# schematic.net
KiCad netlist of a schematic drawn in EAGLE
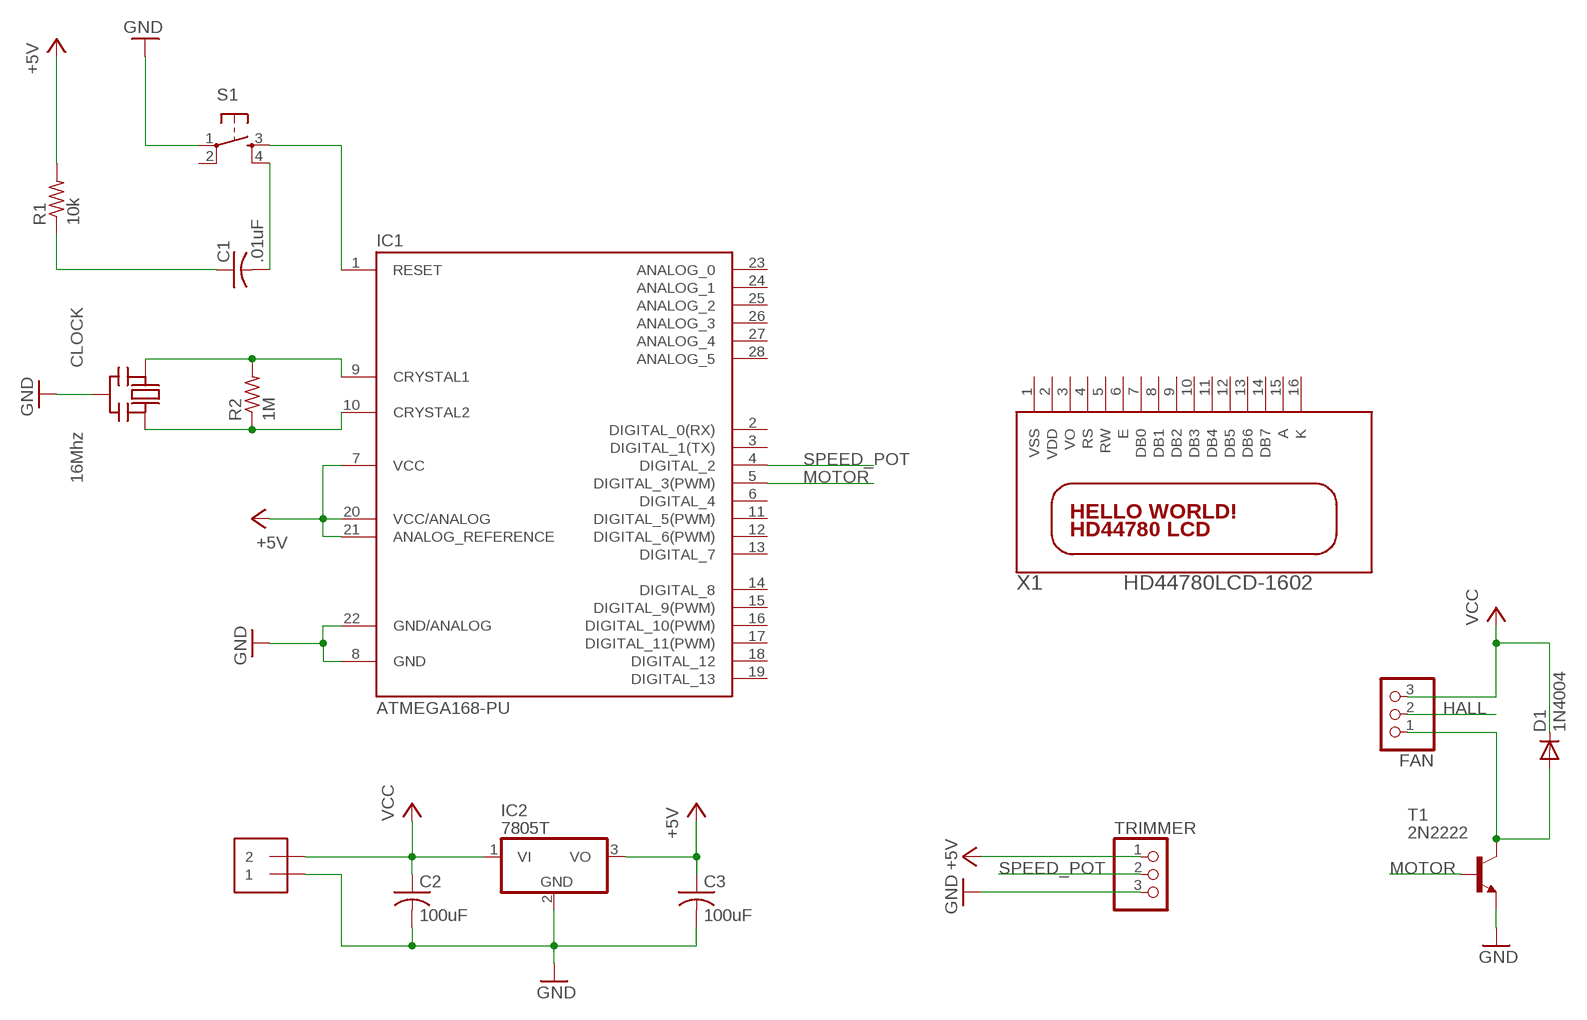
[diagram p0: schematic, sheet 1]

(export (version "E")
  (design (tool "Eeschema 10.0.6"))
  (components
    (comp (ref "C1")
      (value ".01uF")
      (footprint "eagle-import:C025-030X050")
      (libsource (lib "eagle-import") (part "C-US025-030X050"))
    )
    (comp (ref "C2")
      (value "100uF")
      (footprint "eagle-import:C025-030X050")
      (libsource (lib "eagle-import") (part "C-US025-030X050"))
    )
    (comp (ref "C3")
      (value "100uF")
      (footprint "eagle-import:C025-030X050")
      (libsource (lib "eagle-import") (part "C-US025-030X050"))
    )
    (comp (ref "CLOCK")
      (value "16Mhz")
      (footprint "eagle-import:CERM_OSC")
      (libsource (lib "eagle-import") (part "CERMOSCILL-THM"))
    )
    (comp (ref "D1")
      (value "1N4004")
      (footprint "eagle-import:DO41-10")
      (libsource (lib "eagle-import") (part "1N4004"))
    )
    (comp (ref "FAN")
      (value "PINHD-1X3CB")
      (footprint "eagle-import:1X03-CLEANBIG")
      (libsource (lib "eagle-import") (part "PINHD-1X3CB"))
    )
    (comp (ref "IC1")
      (value "ATMEGA168-PU")
      (footprint "eagle-import:DIL28-3")
      (libsource (lib "eagle-import") (part "ATMEGA168-PU"))
    )
    (comp (ref "IC2")
      (value "7805T")
      (footprint "eagle-import:TO220H")
      (libsource (lib "eagle-import") (part "78T05"))
    )
    (comp (ref "POWER")
      (value "1X2-3.5MM")
      (footprint "eagle-import:1X2-3.5MM")
      (libsource (lib "eagle-import") (part "1X2-3.5MM"))
    )
    (comp (ref "R1")
      (value "10k")
      (footprint "eagle-import:0204_7")
      (libsource (lib "eagle-import") (part "R-US_0204/7"))
    )
    (comp (ref "R2")
      (value "1M")
      (footprint "eagle-import:0204_7")
      (libsource (lib "eagle-import") (part "R-US_0204/7"))
    )
    (comp (ref "S1")
      (value "TAC_SWITCHPTH")
      (footprint "eagle-import:TACTILE-PTH")
      (libsource (lib "eagle-import") (part "TAC_SWITCHPTH"))
    )
    (comp (ref "T1")
      (value "2N2222")
      (footprint "eagle-import:TO92-EBC-OVAL")
      (libsource (lib "eagle-import") (part "2N2222"))
    )
    (comp (ref "TRIMMER")
      (value "PINHD-1X3")
      (footprint "eagle-import:1X03")
      (libsource (lib "eagle-import") (part "PINHD-1X3"))
    )
    (comp (ref "X1")
      (value "HD44780LCD-1602")
      (footprint "eagle-import:LCD1602")
      (libsource (lib "eagle-import") (part "HD44780LCD-1602"))
    )
  )
  (nets
    (net (code "1") (name "+5V") (class "Default")
      (node (ref "C3") (pin "1") (pinfunction "1_1") (pintype "passive"))
      (node (ref "IC1") (pin "20") (pinfunction "VCC/ANALOG_20") (pintype "passive"))
      (node (ref "IC1") (pin "21") (pinfunction "ANALOG_REFERENCE_21") (pintype "passive"))
      (node (ref "IC1") (pin "7") (pinfunction "VCC_7") (pintype "power_in"))
      (node (ref "IC2") (pin "3") (pinfunction "VO_3") (pintype "passive"))
      (node (ref "R1") (pin "2") (pinfunction "2_2") (pintype "passive"))
      (node (ref "TRIMMER") (pin "1") (pinfunction "1_1") (pintype "passive"))
    )
    (net (code "2") (name "/HALL") (class "Default")
      (node (ref "FAN") (pin "2") (pinfunction "2_2") (pintype "passive"))
    )
    (net (code "3") (name "/MOTOR") (class "Default")
      (node (ref "IC1") (pin "5") (pinfunction "DIGITAL_3(PWM)_5") (pintype "bidirectional"))
      (node (ref "T1") (pin "B") (pinfunction "B_B") (pintype "passive"))
    )
    (net (code "4") (name "/SPEED_POT") (class "Default")
      (node (ref "IC1") (pin "4") (pinfunction "DIGITAL_2_4") (pintype "bidirectional"))
      (node (ref "TRIMMER") (pin "2") (pinfunction "2_2") (pintype "passive"))
    )
    (net (code "5") (name "/VDD") (class "Default")
      (node (ref "X1") (pin "2") (pinfunction "VDD_2") (pintype "power_in"))
    )
    (net (code "6") (name "/VSS") (class "Default")
      (node (ref "X1") (pin "1") (pinfunction "VSS_1") (pintype "power_in"))
    )
    (net (code "7") (name "GND") (class "Default")
      (node (ref "C2") (pin "2") (pinfunction "2_2") (pintype "passive"))
      (node (ref "C3") (pin "2") (pinfunction "2_2") (pintype "passive"))
      (node (ref "CLOCK") (pin "P$2") (pinfunction "GND_P$2") (pintype "bidirectional"))
      (node (ref "IC1") (pin "22") (pinfunction "GND/ANALOG_22") (pintype "power_in"))
      (node (ref "IC1") (pin "8") (pinfunction "GND_8") (pintype "power_in"))
      (node (ref "IC2") (pin "2") (pinfunction "GND_2") (pintype "passive"))
      (node (ref "POWER") (pin "1") (pinfunction "1_1") (pintype "passive"))
      (node (ref "S1") (pin "1") (pinfunction "1_1") (pintype "passive"))
      (node (ref "T1") (pin "E") (pinfunction "E_E") (pintype "passive"))
      (node (ref "TRIMMER") (pin "3") (pinfunction "3_3") (pintype "passive"))
    )
    (net (code "8") (name "Net-(C1-Pad1)") (class "Default")
      (node (ref "C1") (pin "1") (pinfunction "1_1") (pintype "passive"))
      (node (ref "R1") (pin "1") (pinfunction "1_1") (pintype "passive"))
    )
    (net (code "9") (name "Net-(C1-Pad2)") (class "Default")
      (node (ref "C1") (pin "2") (pinfunction "2_2") (pintype "passive"))
      (node (ref "S1") (pin "4") (pinfunction "4_4") (pintype "passive"))
    )
    (net (code "10") (name "Net-(CLOCK-IN)") (class "Default")
      (node (ref "CLOCK") (pin "P$1") (pinfunction "IN_P$1") (pintype "bidirectional"))
      (node (ref "IC1") (pin "9") (pinfunction "CRYSTAL1_9") (pintype "bidirectional"))
      (node (ref "R2") (pin "2") (pinfunction "2_2") (pintype "passive"))
    )
    (net (code "11") (name "Net-(CLOCK-OUT)") (class "Default")
      (node (ref "CLOCK") (pin "P$3") (pinfunction "OUT_P$3") (pintype "bidirectional"))
      (node (ref "IC1") (pin "10") (pinfunction "CRYSTAL2_10") (pintype "bidirectional"))
      (node (ref "R2") (pin "1") (pinfunction "1_1") (pintype "passive"))
    )
    (net (code "12") (name "Net-(D1-PadA)") (class "Default")
      (node (ref "D1") (pin "A") (pinfunction "A_A") (pintype "passive"))
      (node (ref "FAN") (pin "1") (pinfunction "1_1") (pintype "passive"))
      (node (ref "T1") (pin "C") (pinfunction "C_C") (pintype "passive"))
    )
    (net (code "13") (name "Net-(IC1-RESET)") (class "Default")
      (node (ref "IC1") (pin "1") (pinfunction "RESET_1") (pintype "bidirectional"))
      (node (ref "S1") (pin "3") (pinfunction "3_3") (pintype "passive"))
    )
    (net (code "14") (name "VCC") (class "Default")
      (node (ref "C2") (pin "1") (pinfunction "1_1") (pintype "passive"))
      (node (ref "D1") (pin "C") (pinfunction "C_C") (pintype "passive"))
      (node (ref "FAN") (pin "3") (pinfunction "3_3") (pintype "passive"))
      (node (ref "IC2") (pin "1") (pinfunction "VI_1") (pintype "input"))
      (node (ref "POWER") (pin "2") (pinfunction "2_2") (pintype "passive"))
    )
    (net (code "15") (name "unconnected-(IC1-ANALOG_0-Pad23)") (class "Default")
      (node (ref "IC1") (pin "23") (pinfunction "ANALOG_0_23") (pintype "bidirectional"))
    )
    (net (code "16") (name "unconnected-(IC1-ANALOG_1-Pad24)") (class "Default")
      (node (ref "IC1") (pin "24") (pinfunction "ANALOG_1_24") (pintype "bidirectional"))
    )
    (net (code "17") (name "unconnected-(IC1-ANALOG_2-Pad25)") (class "Default")
      (node (ref "IC1") (pin "25") (pinfunction "ANALOG_2_25") (pintype "bidirectional"))
    )
    (net (code "18") (name "unconnected-(IC1-ANALOG_3-Pad26)") (class "Default")
      (node (ref "IC1") (pin "26") (pinfunction "ANALOG_3_26") (pintype "bidirectional"))
    )
    (net (code "19") (name "unconnected-(IC1-ANALOG_4-Pad27)") (class "Default")
      (node (ref "IC1") (pin "27") (pinfunction "ANALOG_4_27") (pintype "bidirectional"))
    )
    (net (code "20") (name "unconnected-(IC1-ANALOG_5-Pad28)") (class "Default")
      (node (ref "IC1") (pin "28") (pinfunction "ANALOG_5_28") (pintype "bidirectional"))
    )
    (net (code "21") (name "unconnected-(IC1-DIGITAL_0(RX)-Pad2)") (class "Default")
      (node (ref "IC1") (pin "2") (pinfunction "DIGITAL_0(RX)_2") (pintype "bidirectional"))
    )
    (net (code "22") (name "unconnected-(IC1-DIGITAL_1(TX)-Pad3)") (class "Default")
      (node (ref "IC1") (pin "3") (pinfunction "DIGITAL_1(TX)_3") (pintype "bidirectional"))
    )
    (net (code "23") (name "unconnected-(IC1-DIGITAL_4-Pad6)") (class "Default")
      (node (ref "IC1") (pin "6") (pinfunction "DIGITAL_4_6") (pintype "bidirectional"))
    )
    (net (code "24") (name "unconnected-(IC1-DIGITAL_5(PWM)-Pad11)") (class "Default")
      (node (ref "IC1") (pin "11") (pinfunction "DIGITAL_5(PWM)_11") (pintype "bidirectional"))
    )
    (net (code "25") (name "unconnected-(IC1-DIGITAL_6(PWM)-Pad12)") (class "Default")
      (node (ref "IC1") (pin "12") (pinfunction "DIGITAL_6(PWM)_12") (pintype "bidirectional"))
    )
    (net (code "26") (name "unconnected-(IC1-DIGITAL_7-Pad13)") (class "Default")
      (node (ref "IC1") (pin "13") (pinfunction "DIGITAL_7_13") (pintype "bidirectional"))
    )
    (net (code "27") (name "unconnected-(IC1-DIGITAL_8-Pad14)") (class "Default")
      (node (ref "IC1") (pin "14") (pinfunction "DIGITAL_8_14") (pintype "bidirectional"))
    )
    (net (code "28") (name "unconnected-(IC1-DIGITAL_9(PWM)-Pad15)") (class "Default")
      (node (ref "IC1") (pin "15") (pinfunction "DIGITAL_9(PWM)_15") (pintype "bidirectional"))
    )
    (net (code "29") (name "unconnected-(IC1-DIGITAL_10(PWM)-Pad16)") (class "Default")
      (node (ref "IC1") (pin "16") (pinfunction "DIGITAL_10(PWM)_16") (pintype "bidirectional"))
    )
    (net (code "30") (name "unconnected-(IC1-DIGITAL_11(PWM)-Pad17)") (class "Default")
      (node (ref "IC1") (pin "17") (pinfunction "DIGITAL_11(PWM)_17") (pintype "bidirectional"))
    )
    (net (code "31") (name "unconnected-(IC1-DIGITAL_12-Pad18)") (class "Default")
      (node (ref "IC1") (pin "18") (pinfunction "DIGITAL_12_18") (pintype "bidirectional"))
    )
    (net (code "32") (name "unconnected-(IC1-DIGITAL_13-Pad19)") (class "Default")
      (node (ref "IC1") (pin "19") (pinfunction "DIGITAL_13_19") (pintype "bidirectional"))
    )
    (net (code "33") (name "unconnected-(S1-Pad2)") (class "Default")
      (node (ref "S1") (pin "2") (pinfunction "2_2") (pintype "passive"))
    )
    (net (code "34") (name "unconnected-(X1-A-Pad15)") (class "Default")
      (node (ref "X1") (pin "15") (pinfunction "A_15") (pintype "input"))
    )
    (net (code "35") (name "unconnected-(X1-DB0-Pad7)") (class "Default")
      (node (ref "X1") (pin "7") (pinfunction "DB0_7") (pintype "bidirectional"))
    )
    (net (code "36") (name "unconnected-(X1-DB1-Pad8)") (class "Default")
      (node (ref "X1") (pin "8") (pinfunction "DB1_8") (pintype "bidirectional"))
    )
    (net (code "37") (name "unconnected-(X1-DB2-Pad9)") (class "Default")
      (node (ref "X1") (pin "9") (pinfunction "DB2_9") (pintype "bidirectional"))
    )
    (net (code "38") (name "unconnected-(X1-DB3-Pad10)") (class "Default")
      (node (ref "X1") (pin "10") (pinfunction "DB3_10") (pintype "bidirectional"))
    )
    (net (code "39") (name "unconnected-(X1-DB4-Pad11)") (class "Default")
      (node (ref "X1") (pin "11") (pinfunction "DB4_11") (pintype "bidirectional"))
    )
    (net (code "40") (name "unconnected-(X1-DB5-Pad12)") (class "Default")
      (node (ref "X1") (pin "12") (pinfunction "DB5_12") (pintype "bidirectional"))
    )
    (net (code "41") (name "unconnected-(X1-DB6-Pad13)") (class "Default")
      (node (ref "X1") (pin "13") (pinfunction "DB6_13") (pintype "bidirectional"))
    )
    (net (code "42") (name "unconnected-(X1-DB7-Pad14)") (class "Default")
      (node (ref "X1") (pin "14") (pinfunction "DB7_14") (pintype "bidirectional"))
    )
    (net (code "43") (name "unconnected-(X1-E-Pad6)") (class "Default")
      (node (ref "X1") (pin "6") (pinfunction "E_6") (pintype "input"))
    )
    (net (code "44") (name "unconnected-(X1-K-Pad16)") (class "Default")
      (node (ref "X1") (pin "16") (pinfunction "K_16") (pintype "input"))
    )
    (net (code "45") (name "unconnected-(X1-RS-Pad4)") (class "Default")
      (node (ref "X1") (pin "4") (pinfunction "RS_4") (pintype "input"))
    )
    (net (code "46") (name "unconnected-(X1-RW-Pad5)") (class "Default")
      (node (ref "X1") (pin "5") (pinfunction "RW_5") (pintype "input"))
    )
    (net (code "47") (name "unconnected-(X1-VO-Pad3)") (class "Default")
      (node (ref "X1") (pin "3") (pinfunction "VO_3") (pintype "input"))
    )
  )
)
